# proy_10B_SCH_1_v1i1.net
KiCad netlist of a schematic drawn in Altium Designer
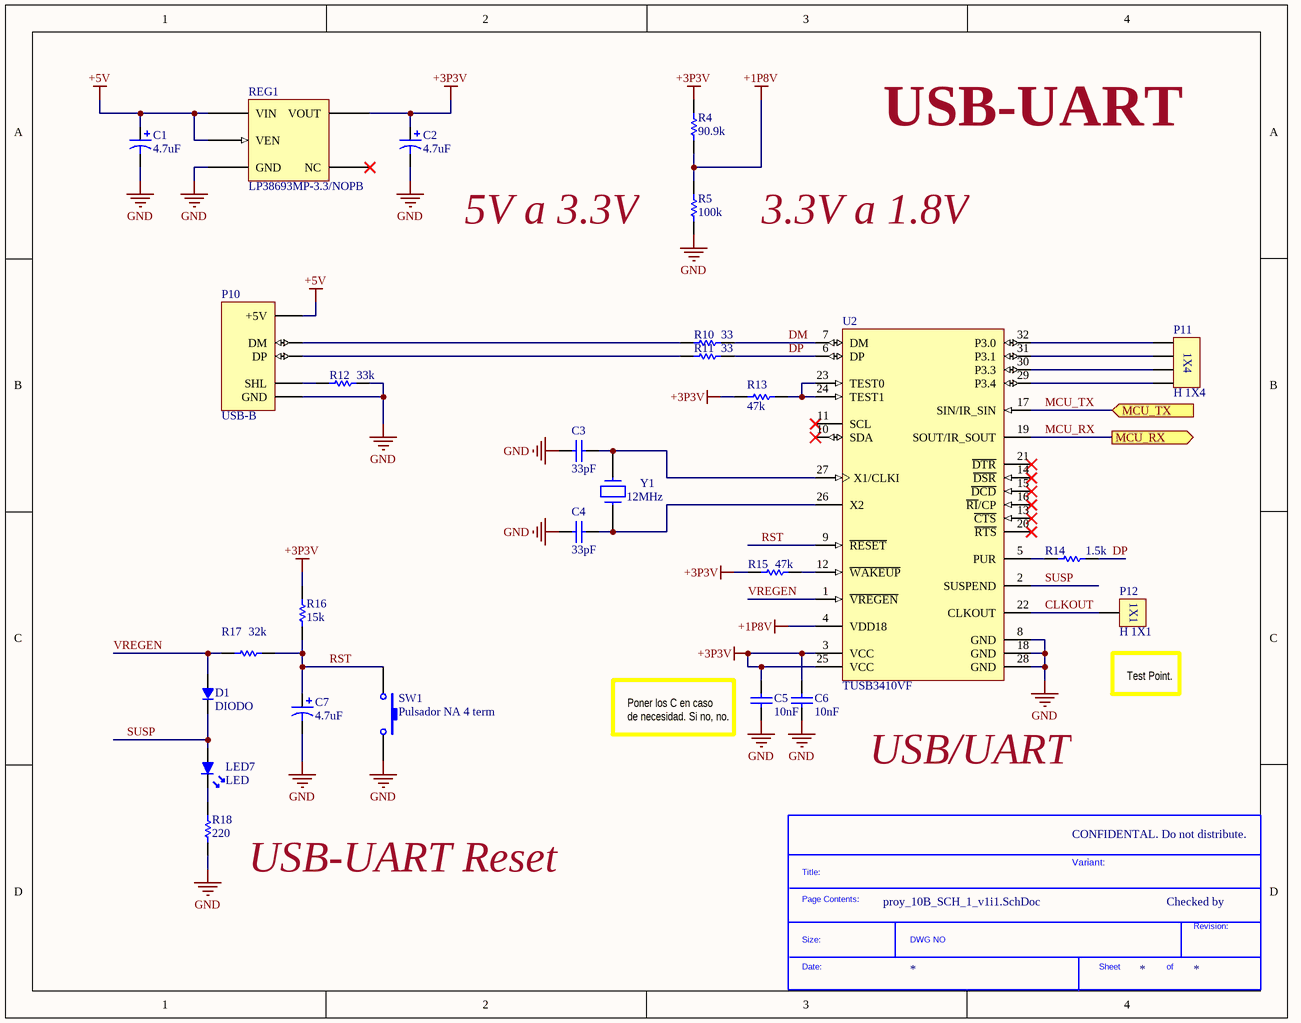
[diagram p0: proy_10B_SCH_1_v1i1.SchDoc]

(export (version "E")
  (design (tool "Eeschema 10.0.6"))
  (components
    (comp (ref "*") (value "SDTitleBlock") (libsource (lib "*") (part "SDTitleBlock")))
    (comp (ref "C1")
      (value "4.7uF")
      (footprint "C 6.3x11")
      (description "Capacitor polarizado.")
      (fields (field (name ".CREATOR") "SR"))
      (libsource (lib "Libreria_Santi") (part "C POL"))
    )
    (comp (ref "C2")
      (value "4.7uF")
      (footprint "C 6.3x11")
      (description "Capacitor polarizado.")
      (fields (field (name ".CREATOR") "SR"))
      (libsource (lib "Libreria_Santi") (part "C POL"))
    )
    (comp (ref "C3")
      (value "33pF")
      (footprint "C 1206")
      (description "Capacitor")
      (fields (field (name ".CREATOR") "SR"))
      (libsource (lib "Libreria_Santi") (part "C"))
    )
    (comp (ref "C4")
      (value "33pF")
      (footprint "C 1206")
      (description "Capacitor")
      (fields (field (name ".CREATOR") "SR"))
      (libsource (lib "Libreria_Santi") (part "C"))
    )
    (comp (ref "C5")
      (value "10nF")
      (footprint "C 1206")
      (description "Capacitor")
      (fields (field (name ".CREATOR") "SR"))
      (libsource (lib "Libreria_Santi") (part "C"))
    )
    (comp (ref "C6")
      (value "10nF")
      (footprint "C 1206")
      (description "Capacitor")
      (fields (field (name ".CREATOR") "SR"))
      (libsource (lib "Libreria_Santi") (part "C"))
    )
    (comp (ref "C7")
      (value "4.7uF")
      (footprint "C 6.3x11")
      (description "Capacitor polarizado.")
      (fields (field (name ".CREATOR") "SR"))
      (libsource (lib "Libreria_Santi") (part "C POL"))
    )
    (comp (ref "D1")
      (value "DIODO")
      (footprint "D 1206")
      (fields (field (name ".CREATOR") "SR") (field (name ".PCBCHECK") "SR") (field (name ".SCHCHECK") "SR"))
      (libsource (lib "Libreria_Santi") (part "DIODO"))
    )
    (comp (ref "LED7")
      (value "LED")
      (footprint "LED 1206")
      (fields (field (name ".CREATOR") "SR"))
      (libsource (lib "Libreria_Santi") (part "LED"))
    )
    (comp (ref "P10")
      (value "USB-B")
      (footprint "USBB")
      (description "Conector USB tipo B")
      (libsource (lib "Libreria_Santi") (part "USB-B"))
    )
    (comp (ref "P11")
      (value "H 1X4")
      (footprint "H 1X4 - Hembra")
      (description "PIN HEADER 1X4")
      (fields (field (name ".CREATOR") "SR"))
      (libsource (lib "Libreria_Santi") (part "H 1X4"))
    )
    (comp (ref "P12")
      (value "H 1X1")
      (footprint "H 1x1")
      (description "PIN HEADER 1X1")
      (fields (field (name ".CREATOR") "SR"))
      (libsource (lib "Libreria_Santi") (part "H 1X1"))
    )
    (comp (ref "R4")
      (value "90.9k")
      (footprint "R 1206")
      (description "Resistencia")
      (fields (field (name ".CREATOR") "SR"))
      (libsource (lib "Libreria_Santi") (part "R"))
    )
    (comp (ref "R5")
      (value "100k")
      (footprint "R 1206")
      (description "Resistencia")
      (fields (field (name ".CREATOR") "SR"))
      (libsource (lib "Libreria_Santi") (part "R"))
    )
    (comp (ref "R10")
      (value "33")
      (footprint "R 1206")
      (description "Resistencia")
      (fields (field (name ".CREATOR") "SR"))
      (libsource (lib "Libreria_Santi") (part "R"))
    )
    (comp (ref "R11")
      (value "33")
      (footprint "R 1206")
      (description "Resistencia")
      (fields (field (name ".CREATOR") "SR"))
      (libsource (lib "Libreria_Santi") (part "R"))
    )
    (comp (ref "R12")
      (value "33k")
      (footprint "R 1206")
      (description "Resistencia")
      (fields (field (name ".CREATOR") "SR"))
      (libsource (lib "Libreria_Santi") (part "R"))
    )
    (comp (ref "R13")
      (value "47k")
      (footprint "R 1206")
      (description "Resistencia")
      (fields (field (name ".CREATOR") "SR"))
      (libsource (lib "Libreria_Santi") (part "R"))
    )
    (comp (ref "R14")
      (value "1.5k")
      (footprint "R 1206")
      (description "Resistencia")
      (fields (field (name ".CREATOR") "SR"))
      (libsource (lib "Libreria_Santi") (part "R"))
    )
    (comp (ref "R15")
      (value "47k")
      (footprint "R 1206")
      (description "Resistencia")
      (fields (field (name ".CREATOR") "SR"))
      (libsource (lib "Libreria_Santi") (part "R"))
    )
    (comp (ref "R16")
      (value "15k")
      (footprint "R 1206")
      (description "Resistencia")
      (fields (field (name ".CREATOR") "SR"))
      (libsource (lib "Libreria_Santi") (part "R"))
    )
    (comp (ref "R17")
      (value "32k")
      (footprint "R 1206")
      (description "Resistencia")
      (fields (field (name ".CREATOR") "SR"))
      (libsource (lib "Libreria_Santi") (part "R"))
    )
    (comp (ref "R18")
      (value "220")
      (footprint "R 1206")
      (description "Resistencia")
      (fields (field (name ".CREATOR") "SR"))
      (libsource (lib "Libreria_Santi") (part "R"))
    )
    (comp (ref "REG1")
      (value "LP38693MP-3.3/NOPB")
      (footprint "SOT223-5")
      (description "IC REG LDO 3.3V 0.5A SOT223-5")
      (fields (field (name "MANUFACTURER") "Texas Instruments"))
      (libsource (lib "Libreria_Santi") (part "LP38693MP-3.3/NOPB"))
    )
    (comp (ref "SW1")
      (value "Pulsador NA 4 term")
      (footprint "TACT SW")
      (fields (field (name ".CREATOR") "G") (field (name ".PCBCHECK") "G") (field (name ".SCHCHECK") "G"))
      (libsource (lib "Libreria_Santi") (part "Pulsador NA 4 term"))
    )
    (comp (ref "U2")
      (value "TUSB3410VF")
      (footprint "TQFP-32")
      (description "IC CONV SERIAL-TO-USB 32-LQFP")
      (fields (field (name "MANUFACTURER") "Texas Instruments"))
      (libsource (lib "Libreria_Santi") (part "TUSB3410VF"))
    )
    (comp (ref "Y1")
      (value "12MHz")
      (footprint "Y TRHU")
      (description "Cristal de cuarzo")
      (fields (field (name ".CREATOR") "G"))
      (libsource (lib "Libreria_Santi") (part "Cristal de Cuarzo"))
    )
  )
  (nets
    (net (code "1") (name "+1P8V") (class "Default")
      (node (ref "R4") (pin "2") (pinfunction "2_2") (pintype "passive"))
      (node (ref "R5") (pin "1") (pinfunction "1_1") (pintype "passive"))
      (node (ref "U2") (pin "4") (pinfunction "VDD18_4") (pintype "power_in"))
    )
    (net (code "2") (name "+3P3V") (class "Default")
      (node (ref "C2") (pin "1") (pinfunction "1_1") (pintype "passive"))
      (node (ref "C5") (pin "2") (pinfunction "2_2") (pintype "passive"))
      (node (ref "C6") (pin "2") (pinfunction "2_2") (pintype "passive"))
      (node (ref "R13") (pin "2") (pinfunction "2_2") (pintype "passive"))
      (node (ref "R15") (pin "2") (pinfunction "2_2") (pintype "passive"))
      (node (ref "R16") (pin "1") (pinfunction "1_1") (pintype "passive"))
      (node (ref "R4") (pin "1") (pinfunction "1_1") (pintype "passive"))
      (node (ref "REG1") (pin "3") (pinfunction "VOUT_3") (pintype "power_in"))
      (node (ref "U2") (pin "25") (pinfunction "VCC_25") (pintype "power_in"))
      (node (ref "U2") (pin "3") (pinfunction "VCC_3") (pintype "power_in"))
    )
    (net (code "3") (name "+5V") (class "Default")
      (node (ref "C1") (pin "1") (pinfunction "1_1") (pintype "passive"))
      (node (ref "P10") (pin "1") (pinfunction "+5V_1") (pintype "power_in"))
      (node (ref "REG1") (pin "1") (pinfunction "VEN_1") (pintype "input"))
      (node (ref "REG1") (pin "4") (pinfunction "VIN_4") (pintype "power_in"))
    )
    (net (code "4") (name "/CLKOUT") (class "Default")
      (node (ref "P12") (pin "1") (pinfunction "1_1") (pintype "passive"))
      (node (ref "U2") (pin "22") (pinfunction "CLKOUT_22") (pintype "tri_state"))
    )
    (net (code "5") (name "/DM") (class "Default")
      (node (ref "R10") (pin "1") (pinfunction "1_1") (pintype "passive"))
      (node (ref "U2") (pin "7") (pinfunction "DM_7") (pintype "bidirectional"))
    )
    (net (code "6") (name "/DP") (class "Default")
      (node (ref "R11") (pin "1") (pinfunction "1_1") (pintype "passive"))
      (node (ref "R14") (pin "1") (pinfunction "1_1") (pintype "passive"))
      (node (ref "U2") (pin "6") (pinfunction "DP_6") (pintype "bidirectional"))
    )
    (net (code "7") (name "/MCU_RX") (class "Default")
      (node (ref "U2") (pin "19") (pinfunction "SOUT/IR_SOUT_19") (pintype "tri_state"))
    )
    (net (code "8") (name "/MCU_TX") (class "Default")
      (node (ref "U2") (pin "17") (pinfunction "SIN/IR_SIN_17") (pintype "input"))
    )
    (net (code "9") (name "/RST") (class "Default")
      (node (ref "C7") (pin "1") (pinfunction "1_1") (pintype "passive"))
      (node (ref "R16") (pin "2") (pinfunction "2_2") (pintype "passive"))
      (node (ref "R17") (pin "1") (pinfunction "1_1") (pintype "passive"))
      (node (ref "SW1") (pin "1") (pinfunction "1_1") (pintype "passive"))
      (node (ref "U2") (pin "9") (pinfunction "~{RESET}_9") (pintype "input"))
    )
    (net (code "10") (name "/SUSP") (class "Default")
      (node (ref "D1") (pin "2") (pinfunction "K_2") (pintype "passive"))
      (node (ref "LED7") (pin "1") (pinfunction "A_1") (pintype "passive"))
      (node (ref "U2") (pin "2") (pinfunction "SUSPEND_2") (pintype "tri_state"))
    )
    (net (code "11") (name "/VREGEN") (class "Default")
      (node (ref "D1") (pin "1") (pinfunction "A_1") (pintype "passive"))
      (node (ref "R17") (pin "2") (pinfunction "2_2") (pintype "passive"))
      (node (ref "U2") (pin "1") (pinfunction "~{VREGEN}_1") (pintype "input"))
    )
    (net (code "12") (name "GND") (class "Default")
      (node (ref "C1") (pin "2") (pinfunction "2_2") (pintype "passive"))
      (node (ref "C2") (pin "2") (pinfunction "2_2") (pintype "passive"))
      (node (ref "C3") (pin "1") (pinfunction "1_1") (pintype "passive"))
      (node (ref "C4") (pin "1") (pinfunction "1_1") (pintype "passive"))
      (node (ref "C5") (pin "1") (pinfunction "1_1") (pintype "passive"))
      (node (ref "C6") (pin "1") (pinfunction "1_1") (pintype "passive"))
      (node (ref "C7") (pin "2") (pinfunction "2_2") (pintype "passive"))
      (node (ref "P10") (pin "4") (pinfunction "GND_4") (pintype "power_in"))
      (node (ref "R12") (pin "1") (pinfunction "1_1") (pintype "passive"))
      (node (ref "R18") (pin "2") (pinfunction "2_2") (pintype "passive"))
      (node (ref "R5") (pin "2") (pinfunction "2_2") (pintype "passive"))
      (node (ref "REG1") (pin "0") (pinfunction "GND_0") (pintype "power_in"))
      (node (ref "SW1") (pin "2") (pinfunction "2_2") (pintype "passive"))
      (node (ref "U2") (pin "18") (pinfunction "GND_18") (pintype "power_in"))
      (node (ref "U2") (pin "28") (pinfunction "GND_28") (pintype "power_in"))
      (node (ref "U2") (pin "8") (pinfunction "GND_8") (pintype "power_in"))
    )
    (net (code "13") (name "Net-(LED7-K)") (class "Default")
      (node (ref "LED7") (pin "2") (pinfunction "K_2") (pintype "passive"))
      (node (ref "R18") (pin "1") (pinfunction "1_1") (pintype "passive"))
    )
    (net (code "14") (name "Net-(P10-DM)") (class "Default")
      (node (ref "P10") (pin "2") (pinfunction "DM_2") (pintype "bidirectional"))
      (node (ref "R10") (pin "2") (pinfunction "2_2") (pintype "passive"))
    )
    (net (code "15") (name "Net-(P10-DP)") (class "Default")
      (node (ref "P10") (pin "3") (pinfunction "DP_3") (pintype "bidirectional"))
      (node (ref "R11") (pin "2") (pinfunction "2_2") (pintype "passive"))
    )
    (net (code "16") (name "Net-(P10-SHL)") (class "Default")
      (node (ref "P10") (pin "0") (pinfunction "SHL_0") (pintype "passive"))
      (node (ref "R12") (pin "2") (pinfunction "2_2") (pintype "passive"))
    )
    (net (code "17") (name "Net-(U2-P3.0)") (class "Default")
      (node (ref "P11") (pin "1") (pinfunction "1_1") (pintype "passive"))
      (node (ref "U2") (pin "32") (pinfunction "P3.0_32") (pintype "bidirectional"))
    )
    (net (code "18") (name "Net-(U2-P3.1)") (class "Default")
      (node (ref "P11") (pin "2") (pinfunction "2_2") (pintype "passive"))
      (node (ref "U2") (pin "31") (pinfunction "P3.1_31") (pintype "bidirectional"))
    )
    (net (code "19") (name "Net-(U2-P3.3)") (class "Default")
      (node (ref "P11") (pin "3") (pinfunction "3_3") (pintype "passive"))
      (node (ref "U2") (pin "30") (pinfunction "P3.3_30") (pintype "bidirectional"))
    )
    (net (code "20") (name "Net-(U2-P3.4)") (class "Default")
      (node (ref "P11") (pin "4") (pinfunction "4_4") (pintype "passive"))
      (node (ref "U2") (pin "29") (pinfunction "P3.4_29") (pintype "bidirectional"))
    )
    (net (code "21") (name "Net-(U2-PUR)") (class "Default")
      (node (ref "R14") (pin "2") (pinfunction "2_2") (pintype "passive"))
      (node (ref "U2") (pin "5") (pinfunction "PUR_5") (pintype "tri_state"))
    )
    (net (code "22") (name "Net-(U2-TEST0)") (class "Default")
      (node (ref "R13") (pin "1") (pinfunction "1_1") (pintype "passive"))
      (node (ref "U2") (pin "23") (pinfunction "TEST0_23") (pintype "input"))
      (node (ref "U2") (pin "24") (pinfunction "TEST1_24") (pintype "input"))
    )
    (net (code "23") (name "Net-(U2-X1{slash}CLKI)") (class "Default")
      (node (ref "C3") (pin "2") (pinfunction "2_2") (pintype "passive"))
      (node (ref "U2") (pin "27") (pinfunction "X1/CLKI_27") (pintype "input"))
      (node (ref "Y1") (pin "2") (pinfunction "2_2") (pintype "passive"))
    )
    (net (code "24") (name "Net-(U2-X2)") (class "Default")
      (node (ref "C4") (pin "2") (pinfunction "2_2") (pintype "passive"))
      (node (ref "U2") (pin "26") (pinfunction "X2_26") (pintype "passive"))
      (node (ref "Y1") (pin "1") (pinfunction "1_1") (pintype "passive"))
    )
    (net (code "25") (name "Net-(U2-~{WAKEUP})") (class "Default")
      (node (ref "R15") (pin "1") (pinfunction "1_1") (pintype "passive"))
      (node (ref "U2") (pin "12") (pinfunction "~{WAKEUP}_12") (pintype "input"))
    )
    (net (code "26") (name "unconnected-(REG1-NC-Pad2)") (class "Default")
      (node (ref "REG1") (pin "2") (pinfunction "NC_2") (pintype "passive+no_connect"))
    )
    (net (code "27") (name "unconnected-(U2-SCL-Pad11)") (class "Default")
      (node (ref "U2") (pin "11") (pinfunction "SCL_11") (pintype "tri_state+no_connect"))
    )
    (net (code "28") (name "unconnected-(U2-SDA-Pad10)") (class "Default")
      (node (ref "U2") (pin "10") (pinfunction "SDA_10") (pintype "bidirectional+no_connect"))
    )
    (net (code "29") (name "unconnected-(U2-~{CTS}-Pad13)") (class "Default")
      (node (ref "U2") (pin "13") (pinfunction "~{CTS}_13") (pintype "input+no_connect"))
    )
    (net (code "30") (name "unconnected-(U2-~{DCD}-Pad15)") (class "Default")
      (node (ref "U2") (pin "15") (pinfunction "~{DCD}_15") (pintype "input+no_connect"))
    )
    (net (code "31") (name "unconnected-(U2-~{DSR}-Pad14)") (class "Default")
      (node (ref "U2") (pin "14") (pinfunction "~{DSR}_14") (pintype "input+no_connect"))
    )
    (net (code "32") (name "unconnected-(U2-~{DTR}-Pad21)") (class "Default")
      (node (ref "U2") (pin "21") (pinfunction "~{DTR}_21") (pintype "tri_state+no_connect"))
    )
    (net (code "33") (name "unconnected-(U2-~{RI}{slash}CP-Pad16)") (class "Default")
      (node (ref "U2") (pin "16") (pinfunction "~{RI}/CP_16") (pintype "input+no_connect"))
    )
    (net (code "34") (name "unconnected-(U2-~{RTS}-Pad20)") (class "Default")
      (node (ref "U2") (pin "20") (pinfunction "~{RTS}_20") (pintype "tri_state+no_connect"))
    )
  )
)
